# smd555.net
KiCad netlist of a schematic drawn in EAGLE
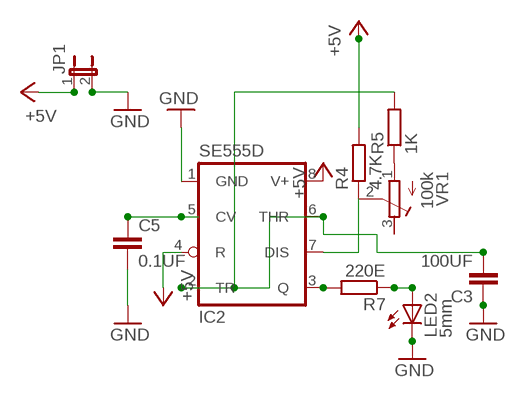
[diagram p0: schematic, sheet 1]

(export (version "E")
  (design (tool "Eeschema 10.0.6"))
  (components
    (comp (ref "C3")
      (value "100UF")
      (footprint "eagle-import:C025-050X050")
      (libsource (lib "eagle-import") (part "C-EU025-050X050"))
    )
    (comp (ref "C5")
      (value "0.1UF")
      (footprint "eagle-import:C025-050X050")
      (libsource (lib "eagle-import") (part "C-EU025-050X050"))
    )
    (comp (ref "IC2")
      (value "SE555D")
      (footprint "eagle-import:SO08")
      (libsource (lib "eagle-import") (part "555DSE"))
    )
    (comp (ref "JP1")
      (value "JP1E")
      (footprint "eagle-import:JP1")
      (libsource (lib "eagle-import") (part "JP1E"))
    )
    (comp (ref "LED2")
      (value "5mm")
      (footprint "eagle-import:LED5MM")
      (libsource (lib "eagle-import") (part "LED5MM"))
    )
    (comp (ref "R4")
      (value "4.7K")
      (footprint "eagle-import:0204_7")
      (libsource (lib "eagle-import") (part "R-EU_0204/7"))
    )
    (comp (ref "R5")
      (value "1K")
      (footprint "eagle-import:0204_7")
      (libsource (lib "eagle-import") (part "R-EU_0204/7"))
    )
    (comp (ref "R7")
      (value "220E")
      (footprint "eagle-import:0204_7")
      (libsource (lib "eagle-import") (part "R-EU_0204/7"))
    )
    (comp (ref "VR1")
      (value "100k")
      (footprint "eagle-import:RTRIM64P")
      (libsource (lib "eagle-import") (part "R-TRIMM64P"))
    )
  )
  (nets
    (net (code "1") (name "+5V") (class "Default")
      (node (ref "IC2") (pin "4") (pinfunction "R_4") (pintype "input"))
      (node (ref "IC2") (pin "8") (pinfunction "V+_8") (pintype "power_in"))
      (node (ref "JP1") (pin "1") (pinfunction "1_1") (pintype "passive"))
      (node (ref "R4") (pin "2") (pinfunction "2_2") (pintype "passive"))
    )
    (net (code "2") (name "GND") (class "Default")
      (node (ref "C3") (pin "1") (pinfunction "1_1") (pintype "passive"))
      (node (ref "C5") (pin "2") (pinfunction "2_2") (pintype "passive"))
      (node (ref "IC2") (pin "1") (pinfunction "GND_1") (pintype "power_in"))
      (node (ref "JP1") (pin "2") (pinfunction "2_2") (pintype "passive"))
      (node (ref "LED2") (pin "K") (pinfunction "C_K") (pintype "passive"))
    )
    (net (code "3") (name "Net-(IC2-CV)") (class "Default")
      (node (ref "C5") (pin "1") (pinfunction "1_1") (pintype "passive"))
      (node (ref "IC2") (pin "5") (pinfunction "CV_5") (pintype "input"))
    )
    (net (code "4") (name "Net-(IC2-DIS)") (class "Default")
      (node (ref "IC2") (pin "7") (pinfunction "DIS_7") (pintype "input"))
      (node (ref "R4") (pin "1") (pinfunction "1_1") (pintype "passive"))
      (node (ref "VR1") (pin "2") (pinfunction "S_2") (pintype "passive"))
    )
    (net (code "5") (name "Net-(IC2-Q)") (class "Default")
      (node (ref "IC2") (pin "3") (pinfunction "Q_3") (pintype "output"))
      (node (ref "R7") (pin "2") (pinfunction "2_2") (pintype "passive"))
    )
    (net (code "6") (name "Net-(IC2-THR)") (class "Default")
      (node (ref "C3") (pin "2") (pinfunction "2_2") (pintype "passive"))
      (node (ref "IC2") (pin "2") (pinfunction "TR_2") (pintype "input"))
      (node (ref "IC2") (pin "6") (pinfunction "THR_6") (pintype "input"))
      (node (ref "R5") (pin "2") (pinfunction "2_2") (pintype "passive"))
    )
    (net (code "7") (name "Net-(LED2-PadA)") (class "Default")
      (node (ref "LED2") (pin "A") (pinfunction "A_A") (pintype "passive"))
      (node (ref "R7") (pin "1") (pinfunction "1_1") (pintype "passive"))
    )
    (net (code "8") (name "Net-(VR1-E)") (class "Default")
      (node (ref "R5") (pin "1") (pinfunction "1_1") (pintype "passive"))
      (node (ref "VR1") (pin "1") (pinfunction "E_1") (pintype "passive"))
    )
    (net (code "9") (name "unconnected-(VR1-A-Pad3)") (class "Default")
      (node (ref "VR1") (pin "3") (pinfunction "A_3") (pintype "passive"))
    )
  )
)
